# SparkFun-OpenPIR-NCS36000.net
KiCad netlist of a schematic drawn in EAGLE
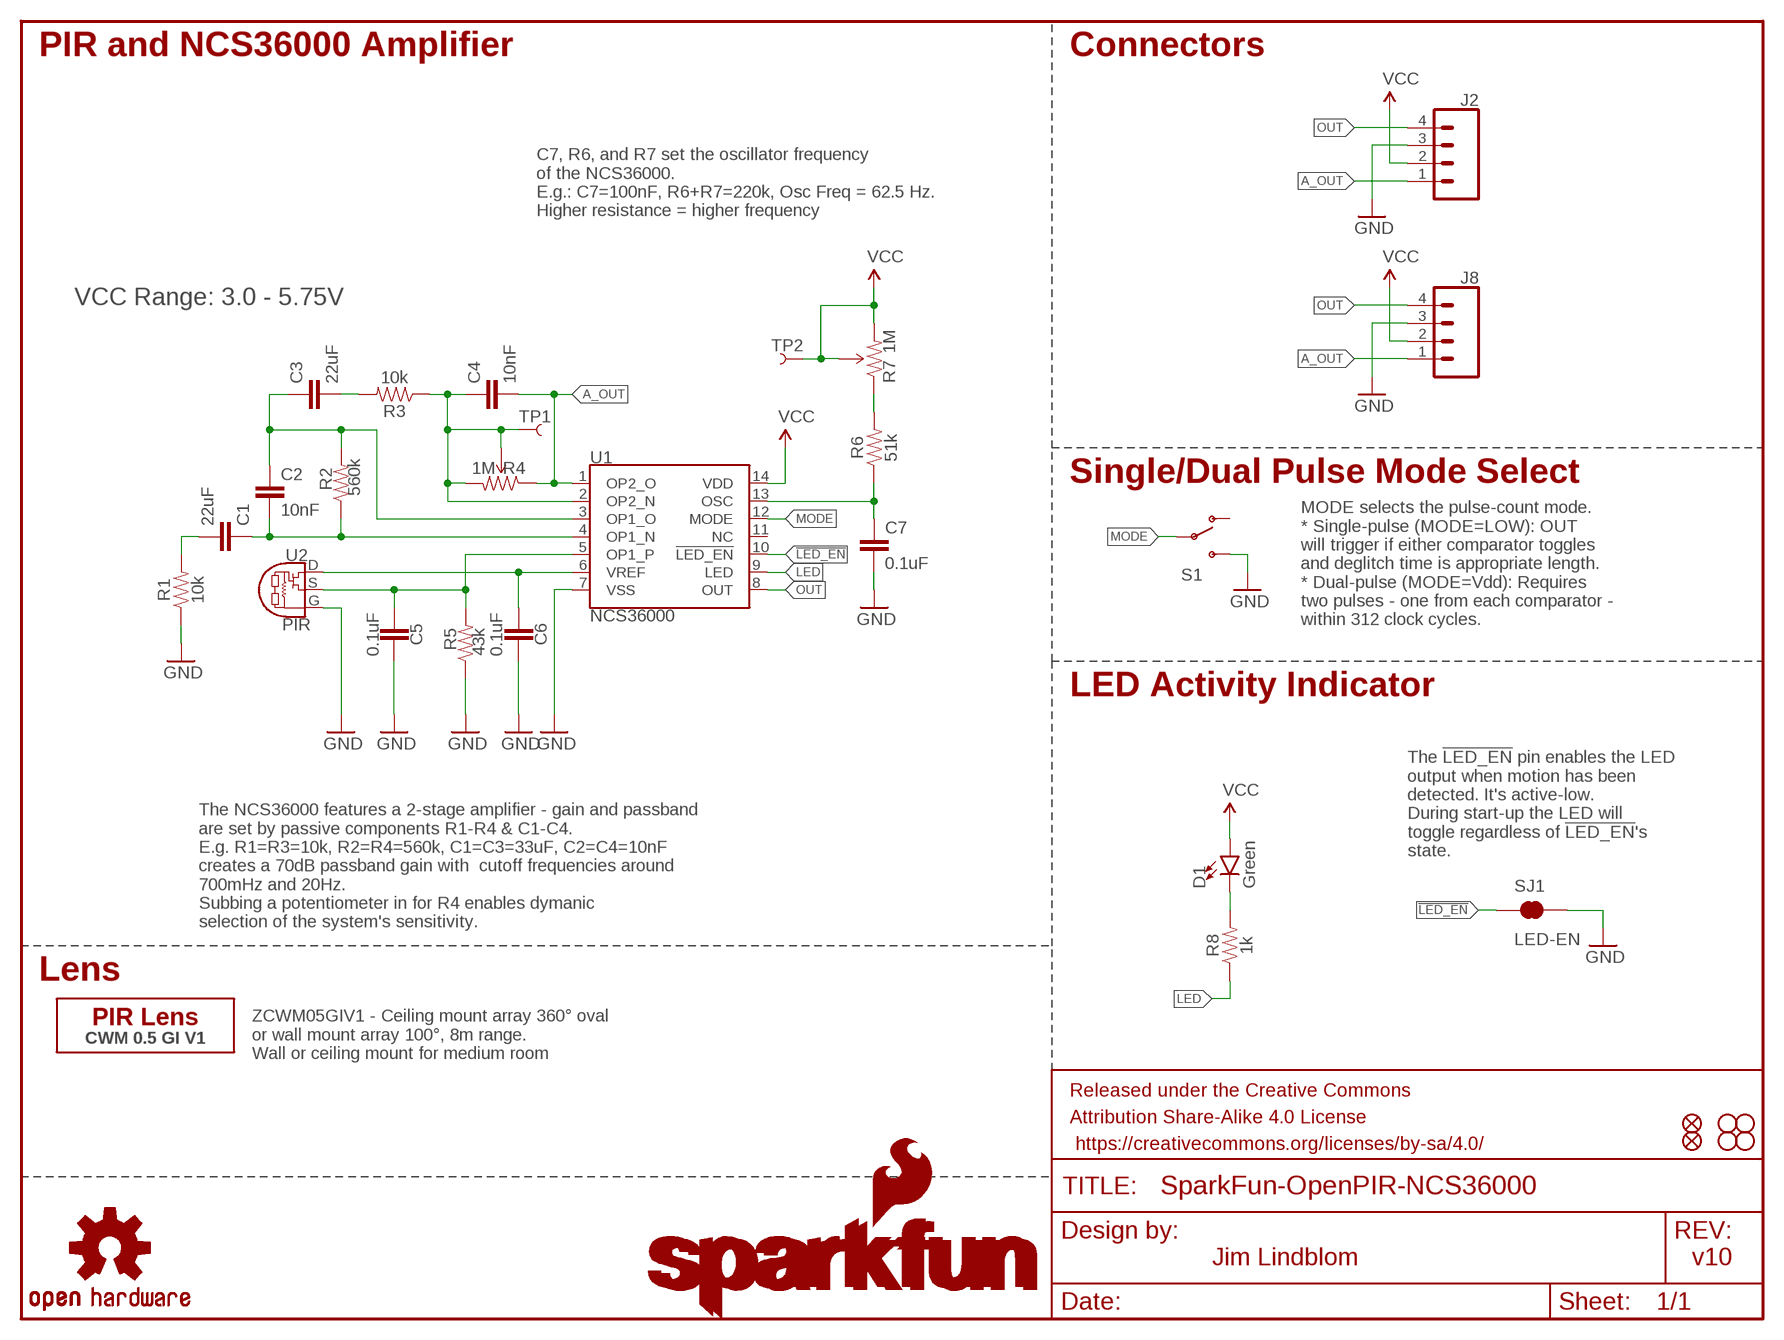
[diagram p0: schematic, sheet 1]

(export (version "E")
  (design (tool "Eeschema 10.0.6"))
  (components
    (comp (ref "C1")
      (value "22uF")
      (footprint "eagle-import:0805")
      (libsource (lib "eagle-import") (part "22UF-0805-6.3V-20%"))
    )
    (comp (ref "C2")
      (value "10nF")
      (footprint "eagle-import:0603")
      (libsource (lib "eagle-import") (part "10NF-0603-50V-10%"))
    )
    (comp (ref "C3")
      (value "22uF")
      (footprint "eagle-import:0805")
      (libsource (lib "eagle-import") (part "22UF-0805-6.3V-20%"))
    )
    (comp (ref "C4")
      (value "10nF")
      (footprint "eagle-import:0603")
      (libsource (lib "eagle-import") (part "10NF-0603-50V-10%"))
    )
    (comp (ref "C5")
      (value "0.1uF")
      (footprint "eagle-import:0603")
      (libsource (lib "eagle-import") (part "0.1UF-0603-25V-(+80/-20%)"))
    )
    (comp (ref "C6")
      (value "0.1uF")
      (footprint "eagle-import:0603")
      (libsource (lib "eagle-import") (part "0.1UF-0603-25V-(+80/-20%)"))
    )
    (comp (ref "C7")
      (value "0.1uF")
      (footprint "eagle-import:0603")
      (libsource (lib "eagle-import") (part "0.1UF-0603-25V-(+80/-20%)"))
    )
    (comp (ref "D1")
      (value "Green")
      (footprint "eagle-import:LED-1206-BOTTOM")
      (libsource (lib "eagle-import") (part "LED-GREEN1206-BOTTOM"))
    )
    (comp (ref "FD1")
      (value "FIDUCIALUFIDUCIAL")
      (footprint "eagle-import:MICRO-FIDUCIAL")
      (libsource (lib "eagle-import") (part "FIDUCIALUFIDUCIAL"))
    )
    (comp (ref "FD2")
      (value "FIDUCIALUFIDUCIAL")
      (footprint "eagle-import:MICRO-FIDUCIAL")
      (libsource (lib "eagle-import") (part "FIDUCIALUFIDUCIAL"))
    )
    (comp (ref "FRAME1")
      (value "FRAME-LETTER")
      (footprint "eagle-import:CREATIVE_COMMONS")
      (libsource (lib "eagle-import") (part "FRAME-LETTER"))
    )
    (comp (ref "H1")
      (value "STAND-OFF")
      (footprint "eagle-import:STAND-OFF")
      (libsource (lib "eagle-import") (part "STAND-OFF"))
    )
    (comp (ref "H2")
      (value "STAND-OFF")
      (footprint "eagle-import:STAND-OFF")
      (libsource (lib "eagle-import") (part "STAND-OFF"))
    )
    (comp (ref "H3")
      (value "STAND-OFF")
      (footprint "eagle-import:STAND-OFF")
      (libsource (lib "eagle-import") (part "STAND-OFF"))
    )
    (comp (ref "H4")
      (value "STAND-OFF")
      (footprint "eagle-import:STAND-OFF")
      (libsource (lib "eagle-import") (part "STAND-OFF"))
    )
    (comp (ref "J2")
      (value "CONN_04JST-PTH-VERT-NS")
      (footprint "eagle-import:JST-4-PTH-VERT-NS")
      (libsource (lib "eagle-import") (part "CONN_04JST-PTH-VERT-NS"))
    )
    (comp (ref "J8")
      (value "CONN_04NO_SILK_ALL_ROUND")
      (footprint "eagle-import:1X04_NO_SILK_ALL_ROUND")
      (libsource (lib "eagle-import") (part "CONN_04NO_SILK_ALL_ROUND"))
    )
    (comp (ref "LOGO1")
      (value "SFE_LOGO_NAME_FLAME.1_INCH")
      (footprint "eagle-import:SFE_LOGO_NAME_FLAME_.1")
      (libsource (lib "eagle-import") (part "SFE_LOGO_NAME_FLAME.1_INCH"))
    )
    (comp (ref "LOGO3")
      (value "SFE_LOGO_NAME.1_INCH")
      (footprint "eagle-import:SFE_LOGO_NAME_.1")
      (libsource (lib "eagle-import") (part "SFE_LOGO_NAME.1_INCH"))
    )
    (comp (ref "LOGO4")
      (value "OSHW-LOGOS")
      (footprint "eagle-import:OSHW-LOGO-S")
      (libsource (lib "eagle-import") (part "OSHW-LOGOS"))
    )
    (comp (ref "R1")
      (value "10k")
      (footprint "eagle-import:0603")
      (libsource (lib "eagle-import") (part "10KOHM-0603-1/10W-1%"))
    )
    (comp (ref "R2")
      (value "560k")
      (footprint "eagle-import:0603")
      (libsource (lib "eagle-import") (part "560KOHM-0603-1/10W-5%"))
    )
    (comp (ref "R3")
      (value "10k")
      (footprint "eagle-import:0603")
      (libsource (lib "eagle-import") (part "10KOHM-0603-1/10W-1%"))
    )
    (comp (ref "R4")
      (value "1M")
      (footprint "eagle-import:TRIMPOT-TC33X")
      (libsource (lib "eagle-import") (part "TRIMPOTTX33X-1M"))
    )
    (comp (ref "R5")
      (value "43k")
      (footprint "eagle-import:0603")
      (libsource (lib "eagle-import") (part "43KOHM-0603-1/10W-1%"))
    )
    (comp (ref "R6")
      (value "51k")
      (footprint "eagle-import:0603")
      (libsource (lib "eagle-import") (part "51KOHM-0603-1/10W-1%"))
    )
    (comp (ref "R7")
      (value "1M")
      (footprint "eagle-import:TRIMPOT-TC33X")
      (libsource (lib "eagle-import") (part "TRIMPOTTX33X-1M"))
    )
    (comp (ref "R8")
      (value "1k")
      (footprint "eagle-import:0603")
      (libsource (lib "eagle-import") (part "1KOHM-0603-1/10W-1%"))
    )
    (comp (ref "S1")
      (value "SWITCH-SPDT-SMD-A")
      (footprint "eagle-import:SWITCH-SPST-SMD-A")
      (libsource (lib "eagle-import") (part "SWITCH-SPDT-SMD-A"))
    )
    (comp (ref "SJ1")
      (value "LED-EN")
      (footprint "eagle-import:SJ_2S")
      (libsource (lib "eagle-import") (part "SOLDERJUMPERNC"))
    )
    (comp (ref "TP1")
      (value "TEST-POINT3X5")
      (footprint "eagle-import:PAD.03X.05")
      (libsource (lib "eagle-import") (part "TEST-POINT3X5"))
    )
    (comp (ref "TP2")
      (value "TEST-POINT3X5")
      (footprint "eagle-import:PAD.03X.05")
      (libsource (lib "eagle-import") (part "TEST-POINT3X5"))
    )
    (comp (ref "U$1")
      (value "CWM 0.5 GI V1")
      (footprint "eagle-import:LENS-CWM-0.5-GI-V1")
      (libsource (lib "eagle-import") (part "PIR-LENSCWM-0.5-GI-V1"))
    )
    (comp (ref "U1")
      (value "NCS36000")
      (footprint "eagle-import:SO14")
      (libsource (lib "eagle-import") (part "NCS36000"))
    )
    (comp (ref "U2")
      (value "PIR")
      (footprint "eagle-import:PIR")
      (libsource (lib "eagle-import") (part "PIR"))
    )
  )
  (nets
    (net (code "1") (name "/~{LED_EN}") (class "Default")
      (node (ref "SJ1") (pin "1") (pinfunction "1_1") (pintype "passive"))
      (node (ref "U1") (pin "10") (pinfunction "~{LED_EN}_10") (pintype "bidirectional"))
    )
    (net (code "2") (name "A_OUT") (class "Default")
      (node (ref "C4") (pin "2") (pinfunction "2_2") (pintype "passive"))
      (node (ref "J2") (pin "1") (pinfunction "1_1") (pintype "passive"))
      (node (ref "J8") (pin "1") (pinfunction "1_1") (pintype "passive"))
      (node (ref "R4") (pin "1") (pinfunction "CCW_1") (pintype "passive"))
      (node (ref "U1") (pin "1") (pinfunction "OP2_O_1") (pintype "bidirectional"))
    )
    (net (code "3") (name "GND") (class "Default")
      (node (ref "C5") (pin "2") (pinfunction "2_2") (pintype "passive"))
      (node (ref "C6") (pin "2") (pinfunction "2_2") (pintype "passive"))
      (node (ref "C7") (pin "2") (pinfunction "2_2") (pintype "passive"))
      (node (ref "J2") (pin "3") (pinfunction "3_3") (pintype "passive"))
      (node (ref "J8") (pin "3") (pinfunction "3_3") (pintype "passive"))
      (node (ref "R1") (pin "1") (pinfunction "1_1") (pintype "passive"))
      (node (ref "R5") (pin "1") (pinfunction "1_1") (pintype "passive"))
      (node (ref "S1") (pin "3") (pinfunction "S_3") (pintype "passive"))
      (node (ref "SJ1") (pin "2") (pinfunction "2_2") (pintype "passive"))
      (node (ref "U1") (pin "7") (pinfunction "VSS_7") (pintype "bidirectional"))
      (node (ref "U2") (pin "G") (pinfunction "G_G") (pintype "bidirectional"))
    )
    (net (code "4") (name "LED") (class "Default")
      (node (ref "R8") (pin "1") (pinfunction "1_1") (pintype "passive"))
      (node (ref "U1") (pin "9") (pinfunction "LED_9") (pintype "bidirectional"))
    )
    (net (code "5") (name "MODE") (class "Default")
      (node (ref "S1") (pin "2") (pinfunction "P_2") (pintype "passive"))
      (node (ref "U1") (pin "12") (pinfunction "MODE_12") (pintype "bidirectional"))
    )
    (net (code "6") (name "Net-(C1-Pad2)") (class "Default")
      (node (ref "C1") (pin "2") (pinfunction "2_2") (pintype "passive"))
      (node (ref "R1") (pin "2") (pinfunction "2_2") (pintype "passive"))
    )
    (net (code "7") (name "Net-(C3-Pad2)") (class "Default")
      (node (ref "C3") (pin "2") (pinfunction "2_2") (pintype "passive"))
      (node (ref "R3") (pin "2") (pinfunction "2_2") (pintype "passive"))
    )
    (net (code "8") (name "Net-(D1-PadC)") (class "Default")
      (node (ref "D1") (pin "C") (pinfunction "C_C") (pintype "passive"))
      (node (ref "R8") (pin "2") (pinfunction "2_2") (pintype "passive"))
    )
    (net (code "9") (name "Net-(R4-CW)") (class "Default")
      (node (ref "C4") (pin "1") (pinfunction "1_1") (pintype "passive"))
      (node (ref "R3") (pin "1") (pinfunction "1_1") (pintype "passive"))
      (node (ref "R4") (pin "2") (pinfunction "WIPER_2") (pintype "passive"))
      (node (ref "R4") (pin "3") (pinfunction "CW_3") (pintype "passive"))
      (node (ref "TP1") (pin "P$1") (pinfunction "1_P$1") (pintype "bidirectional"))
      (node (ref "U1") (pin "2") (pinfunction "OP2_N_2") (pintype "bidirectional"))
    )
    (net (code "10") (name "Net-(R7-CCW)") (class "Default")
      (node (ref "R6") (pin "2") (pinfunction "2_2") (pintype "passive"))
      (node (ref "R7") (pin "1") (pinfunction "CCW_1") (pintype "passive"))
    )
    (net (code "11") (name "Net-(U1-OP1_N)") (class "Default")
      (node (ref "C1") (pin "1") (pinfunction "1_1") (pintype "passive"))
      (node (ref "C2") (pin "2") (pinfunction "2_2") (pintype "passive"))
      (node (ref "R2") (pin "1") (pinfunction "1_1") (pintype "passive"))
      (node (ref "U1") (pin "4") (pinfunction "OP1_N_4") (pintype "bidirectional"))
    )
    (net (code "12") (name "Net-(U1-OP1_O)") (class "Default")
      (node (ref "C2") (pin "1") (pinfunction "1_1") (pintype "passive"))
      (node (ref "C3") (pin "1") (pinfunction "1_1") (pintype "passive"))
      (node (ref "R2") (pin "2") (pinfunction "2_2") (pintype "passive"))
      (node (ref "U1") (pin "3") (pinfunction "OP1_O_3") (pintype "bidirectional"))
    )
    (net (code "13") (name "Net-(U1-OP1_P)") (class "Default")
      (node (ref "C5") (pin "1") (pinfunction "1_1") (pintype "passive"))
      (node (ref "R5") (pin "2") (pinfunction "2_2") (pintype "passive"))
      (node (ref "U1") (pin "5") (pinfunction "OP1_P_5") (pintype "bidirectional"))
      (node (ref "U2") (pin "S") (pinfunction "S_S") (pintype "bidirectional"))
    )
    (net (code "14") (name "Net-(U1-OSC)") (class "Default")
      (node (ref "C7") (pin "1") (pinfunction "1_1") (pintype "passive"))
      (node (ref "R6") (pin "1") (pinfunction "1_1") (pintype "passive"))
      (node (ref "U1") (pin "13") (pinfunction "OSC_13") (pintype "bidirectional"))
    )
    (net (code "15") (name "Net-(U1-VREF)") (class "Default")
      (node (ref "C6") (pin "1") (pinfunction "1_1") (pintype "passive"))
      (node (ref "U1") (pin "6") (pinfunction "VREF_6") (pintype "bidirectional"))
      (node (ref "U2") (pin "D") (pinfunction "D_D") (pintype "bidirectional"))
    )
    (net (code "16") (name "OUT") (class "Default")
      (node (ref "J2") (pin "4") (pinfunction "4_4") (pintype "passive"))
      (node (ref "J8") (pin "4") (pinfunction "4_4") (pintype "passive"))
      (node (ref "U1") (pin "8") (pinfunction "OUT_8") (pintype "bidirectional"))
    )
    (net (code "17") (name "VCC") (class "Default")
      (node (ref "D1") (pin "A") (pinfunction "A_A") (pintype "passive"))
      (node (ref "J2") (pin "2") (pinfunction "2_2") (pintype "passive"))
      (node (ref "J8") (pin "2") (pinfunction "2_2") (pintype "passive"))
      (node (ref "R7") (pin "2") (pinfunction "WIPER_2") (pintype "passive"))
      (node (ref "R7") (pin "3") (pinfunction "CW_3") (pintype "passive"))
      (node (ref "TP2") (pin "P$1") (pinfunction "1_P$1") (pintype "bidirectional"))
      (node (ref "U1") (pin "14") (pinfunction "VDD_14") (pintype "bidirectional"))
    )
    (net (code "18") (name "unconnected-(S1-O-Pad1)") (class "Default")
      (node (ref "S1") (pin "1") (pinfunction "O_1") (pintype "passive"))
    )
    (net (code "19") (name "unconnected-(U1-NC-Pad11)") (class "Default")
      (node (ref "U1") (pin "11") (pinfunction "NC_11") (pintype "bidirectional"))
    )
  )
)
